# BPU_display-v1d-28inch.net
KiCad netlist of a schematic drawn in EAGLE
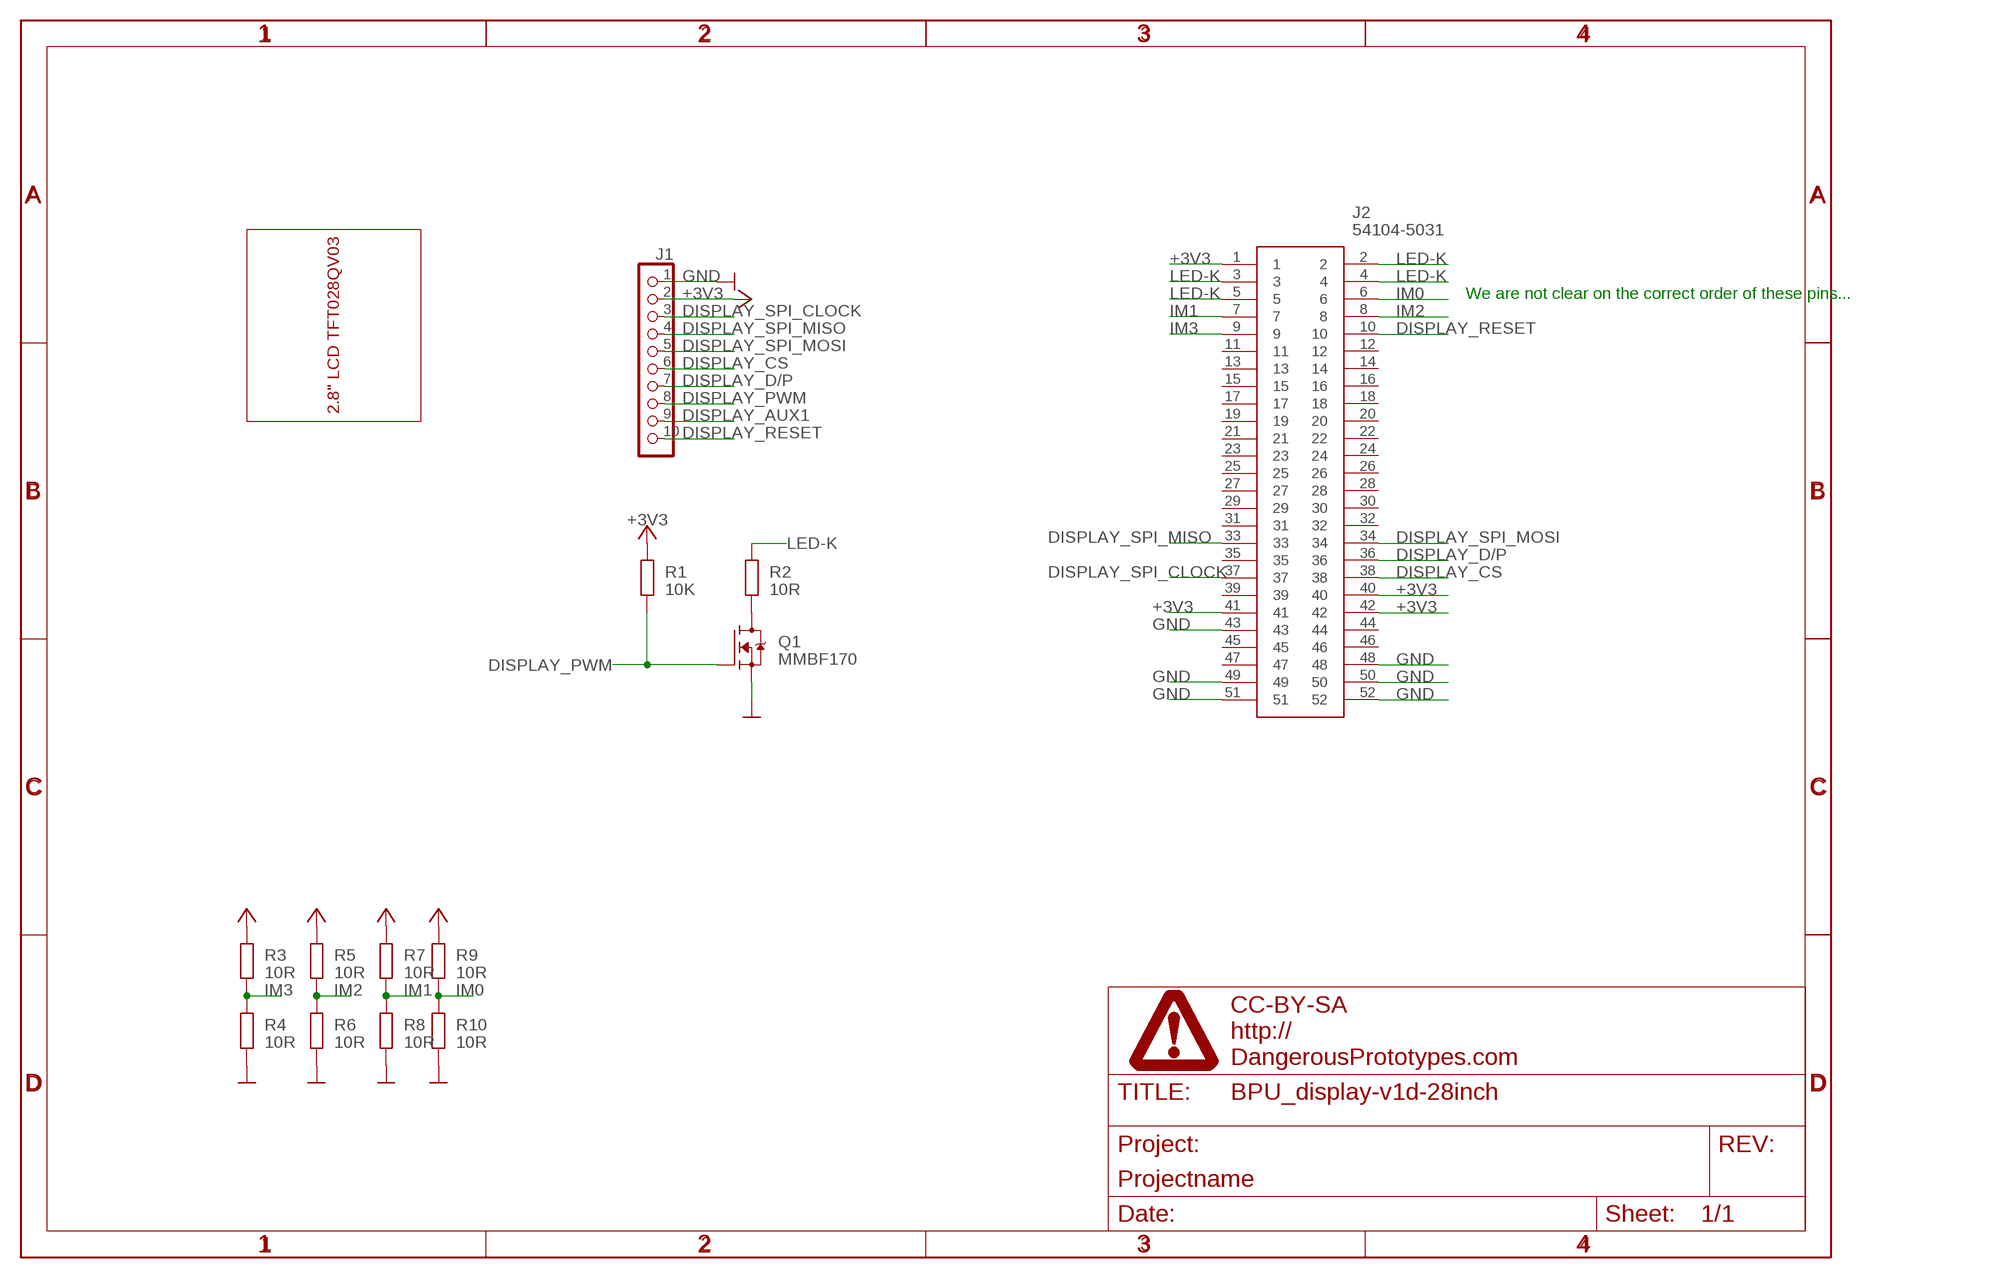
[diagram p0: schematic, sheet 1]

(export (version "E")
  (design (tool "Eeschema 10.0.6"))
  (components
    (comp (ref "J1")
      (value "CON-FPC_X05B20L10T")
      (footprint "eagle-import:X05B20L10T")
      (libsource (lib "eagle-import") (part "CON-FPC_X05B20L10T"))
    )
    (comp (ref "J2")
      (value "54104-5031")
      (footprint "eagle-import:541045031")
      (fields (field (name "MOUSER_PART_NUMBER") "538-54104-5031"))
      (libsource (lib "eagle-import") (part "54104-5031"))
    )
    (comp (ref "PAGE1")
      (value "FRAME_DINA4_L")
      (footprint "eagle-import:DP_LOGO")
      (fields
        (field (name "LICENSE") "CC-BY-SA")
        (field (name "URL1") "http://")
        (field (name "URL2") "DangerousPrototypes.com")
        (field (name "PROJECT") "Projectname")
      )
      (libsource (lib "eagle-import") (part "FRAME_DINA4_L"))
    )
    (comp (ref "Q1")
      (value "MMBF170")
      (footprint "eagle-import:SOT-23")
      (libsource (lib "eagle-import") (part "TRANSISTOR_FET_BS170-SOT-23"))
    )
    (comp (ref "R1")
      (value "10K")
      (footprint "eagle-import:R0603")
      (libsource (lib "eagle-import") (part "R-EU_R0603"))
    )
    (comp (ref "R2")
      (value "10R")
      (footprint "eagle-import:R0603")
      (libsource (lib "eagle-import") (part "R-EU_R0603"))
    )
    (comp (ref "R3")
      (value "10R")
      (footprint "eagle-import:R0603")
      (libsource (lib "eagle-import") (part "R-EU_R0603"))
    )
    (comp (ref "R4")
      (value "10R")
      (footprint "eagle-import:R0603")
      (libsource (lib "eagle-import") (part "R-EU_R0603"))
    )
    (comp (ref "R5")
      (value "10R")
      (footprint "eagle-import:R0603")
      (libsource (lib "eagle-import") (part "R-EU_R0603"))
    )
    (comp (ref "R6")
      (value "10R")
      (footprint "eagle-import:R0603")
      (libsource (lib "eagle-import") (part "R-EU_R0603"))
    )
    (comp (ref "R7")
      (value "10R")
      (footprint "eagle-import:R0603")
      (libsource (lib "eagle-import") (part "R-EU_R0603"))
    )
    (comp (ref "R8")
      (value "10R")
      (footprint "eagle-import:R0603")
      (libsource (lib "eagle-import") (part "R-EU_R0603"))
    )
    (comp (ref "R9")
      (value "10R")
      (footprint "eagle-import:R0603")
      (libsource (lib "eagle-import") (part "R-EU_R0603"))
    )
    (comp (ref "R10")
      (value "10R")
      (footprint "eagle-import:R0603")
      (libsource (lib "eagle-import") (part "R-EU_R0603"))
    )
    (comp (ref "U$1")
      (value "LCDS")
      (footprint "eagle-import:2.8INCHLCD")
      (libsource (lib "eagle-import") (part "LCDS"))
    )
  )
  (nets
    (net (code "1") (name "/DISPLAY_AUX1") (class "Default")
      (node (ref "J1") (pin "9") (pinfunction "9_9") (pintype "passive"))
    )
    (net (code "2") (name "/DISPLAY_CS") (class "Default")
      (node (ref "J1") (pin "6") (pinfunction "6_6") (pintype "passive"))
      (node (ref "J2") (pin "38") (pinfunction "38_38") (pintype "bidirectional"))
    )
    (net (code "3") (name "/DISPLAY_D{slash}P") (class "Default")
      (node (ref "J1") (pin "7") (pinfunction "7_7") (pintype "passive"))
      (node (ref "J2") (pin "36") (pinfunction "36_36") (pintype "bidirectional"))
    )
    (net (code "4") (name "/DISPLAY_PWM") (class "Default")
      (node (ref "J1") (pin "8") (pinfunction "8_8") (pintype "passive"))
      (node (ref "Q1") (pin "1") (pinfunction "G_1") (pintype "passive"))
      (node (ref "R1") (pin "1") (pinfunction "1_1") (pintype "passive"))
    )
    (net (code "5") (name "/DISPLAY_RESET") (class "Default")
      (node (ref "J1") (pin "10") (pinfunction "10_10") (pintype "passive"))
      (node (ref "J2") (pin "10") (pinfunction "10_10") (pintype "bidirectional"))
    )
    (net (code "6") (name "/DISPLAY_SPI_CLOCK") (class "Default")
      (node (ref "J1") (pin "3") (pinfunction "3_3") (pintype "passive"))
      (node (ref "J2") (pin "37") (pinfunction "37_37") (pintype "bidirectional"))
    )
    (net (code "7") (name "/DISPLAY_SPI_MISO") (class "Default")
      (node (ref "J1") (pin "4") (pinfunction "4_4") (pintype "passive"))
      (node (ref "J2") (pin "33") (pinfunction "33_33") (pintype "bidirectional"))
    )
    (net (code "8") (name "/DISPLAY_SPI_MOSI") (class "Default")
      (node (ref "J1") (pin "5") (pinfunction "5_5") (pintype "passive"))
      (node (ref "J2") (pin "34") (pinfunction "34_34") (pintype "bidirectional"))
    )
    (net (code "9") (name "/IM0") (class "Default")
      (node (ref "J2") (pin "6") (pinfunction "6_6") (pintype "bidirectional"))
      (node (ref "R10") (pin "2") (pinfunction "2_2") (pintype "passive"))
      (node (ref "R9") (pin "1") (pinfunction "1_1") (pintype "passive"))
    )
    (net (code "10") (name "/IM1") (class "Default")
      (node (ref "J2") (pin "7") (pinfunction "7_7") (pintype "bidirectional"))
      (node (ref "R7") (pin "1") (pinfunction "1_1") (pintype "passive"))
      (node (ref "R8") (pin "2") (pinfunction "2_2") (pintype "passive"))
    )
    (net (code "11") (name "/IM2") (class "Default")
      (node (ref "J2") (pin "8") (pinfunction "8_8") (pintype "bidirectional"))
      (node (ref "R5") (pin "1") (pinfunction "1_1") (pintype "passive"))
      (node (ref "R6") (pin "2") (pinfunction "2_2") (pintype "passive"))
    )
    (net (code "12") (name "/IM3") (class "Default")
      (node (ref "J2") (pin "9") (pinfunction "9_9") (pintype "bidirectional"))
      (node (ref "R3") (pin "1") (pinfunction "1_1") (pintype "passive"))
      (node (ref "R4") (pin "2") (pinfunction "2_2") (pintype "passive"))
    )
    (net (code "13") (name "/LED-K") (class "Default")
      (node (ref "J2") (pin "2") (pinfunction "2_2") (pintype "bidirectional"))
      (node (ref "J2") (pin "3") (pinfunction "3_3") (pintype "bidirectional"))
      (node (ref "J2") (pin "4") (pinfunction "4_4") (pintype "bidirectional"))
      (node (ref "J2") (pin "5") (pinfunction "5_5") (pintype "bidirectional"))
      (node (ref "R2") (pin "2") (pinfunction "2_2") (pintype "passive"))
    )
    (net (code "14") (name "Net-(Q1-D)") (class "Default")
      (node (ref "Q1") (pin "3") (pinfunction "D_3") (pintype "passive"))
      (node (ref "R2") (pin "1") (pinfunction "1_1") (pintype "passive"))
    )
    (net (code "15") (name "SUPPLY_+3V3") (class "Default")
      (node (ref "J1") (pin "2") (pinfunction "2_2") (pintype "passive"))
      (node (ref "J2") (pin "1") (pinfunction "1_1") (pintype "bidirectional"))
      (node (ref "J2") (pin "40") (pinfunction "40_40") (pintype "bidirectional"))
      (node (ref "J2") (pin "41") (pinfunction "41_41") (pintype "bidirectional"))
      (node (ref "J2") (pin "42") (pinfunction "42_42") (pintype "bidirectional"))
      (node (ref "R1") (pin "2") (pinfunction "2_2") (pintype "passive"))
      (node (ref "R3") (pin "2") (pinfunction "2_2") (pintype "passive"))
      (node (ref "R5") (pin "2") (pinfunction "2_2") (pintype "passive"))
      (node (ref "R7") (pin "2") (pinfunction "2_2") (pintype "passive"))
      (node (ref "R9") (pin "2") (pinfunction "2_2") (pintype "passive"))
    )
    (net (code "16") (name "SUPPLY_GND") (class "Default")
      (node (ref "J1") (pin "1") (pinfunction "1_1") (pintype "passive"))
      (node (ref "J2") (pin "43") (pinfunction "43_43") (pintype "bidirectional"))
      (node (ref "J2") (pin "48") (pinfunction "48_48") (pintype "bidirectional"))
      (node (ref "J2") (pin "49") (pinfunction "49_49") (pintype "bidirectional"))
      (node (ref "J2") (pin "50") (pinfunction "50_50") (pintype "bidirectional"))
      (node (ref "J2") (pin "51") (pinfunction "51_51") (pintype "bidirectional"))
      (node (ref "J2") (pin "52") (pinfunction "52_52") (pintype "bidirectional"))
      (node (ref "Q1") (pin "2") (pinfunction "S_2") (pintype "passive"))
      (node (ref "R10") (pin "1") (pinfunction "1_1") (pintype "passive"))
      (node (ref "R4") (pin "1") (pinfunction "1_1") (pintype "passive"))
      (node (ref "R6") (pin "1") (pinfunction "1_1") (pintype "passive"))
      (node (ref "R8") (pin "1") (pinfunction "1_1") (pintype "passive"))
    )
    (net (code "17") (name "unconnected-(J2-Pad11)") (class "Default")
      (node (ref "J2") (pin "11") (pinfunction "11_11") (pintype "bidirectional"))
    )
    (net (code "18") (name "unconnected-(J2-Pad12)") (class "Default")
      (node (ref "J2") (pin "12") (pinfunction "12_12") (pintype "bidirectional"))
    )
    (net (code "19") (name "unconnected-(J2-Pad13)") (class "Default")
      (node (ref "J2") (pin "13") (pinfunction "13_13") (pintype "bidirectional"))
    )
    (net (code "20") (name "unconnected-(J2-Pad14)") (class "Default")
      (node (ref "J2") (pin "14") (pinfunction "14_14") (pintype "bidirectional"))
    )
    (net (code "21") (name "unconnected-(J2-Pad15)") (class "Default")
      (node (ref "J2") (pin "15") (pinfunction "15_15") (pintype "bidirectional"))
    )
    (net (code "22") (name "unconnected-(J2-Pad16)") (class "Default")
      (node (ref "J2") (pin "16") (pinfunction "16_16") (pintype "bidirectional"))
    )
    (net (code "23") (name "unconnected-(J2-Pad17)") (class "Default")
      (node (ref "J2") (pin "17") (pinfunction "17_17") (pintype "bidirectional"))
    )
    (net (code "24") (name "unconnected-(J2-Pad18)") (class "Default")
      (node (ref "J2") (pin "18") (pinfunction "18_18") (pintype "bidirectional"))
    )
    (net (code "25") (name "unconnected-(J2-Pad19)") (class "Default")
      (node (ref "J2") (pin "19") (pinfunction "19_19") (pintype "bidirectional"))
    )
    (net (code "26") (name "unconnected-(J2-Pad20)") (class "Default")
      (node (ref "J2") (pin "20") (pinfunction "20_20") (pintype "bidirectional"))
    )
    (net (code "27") (name "unconnected-(J2-Pad21)") (class "Default")
      (node (ref "J2") (pin "21") (pinfunction "21_21") (pintype "bidirectional"))
    )
    (net (code "28") (name "unconnected-(J2-Pad22)") (class "Default")
      (node (ref "J2") (pin "22") (pinfunction "22_22") (pintype "bidirectional"))
    )
    (net (code "29") (name "unconnected-(J2-Pad23)") (class "Default")
      (node (ref "J2") (pin "23") (pinfunction "23_23") (pintype "bidirectional"))
    )
    (net (code "30") (name "unconnected-(J2-Pad24)") (class "Default")
      (node (ref "J2") (pin "24") (pinfunction "24_24") (pintype "bidirectional"))
    )
    (net (code "31") (name "unconnected-(J2-Pad25)") (class "Default")
      (node (ref "J2") (pin "25") (pinfunction "25_25") (pintype "bidirectional"))
    )
    (net (code "32") (name "unconnected-(J2-Pad26)") (class "Default")
      (node (ref "J2") (pin "26") (pinfunction "26_26") (pintype "bidirectional"))
    )
    (net (code "33") (name "unconnected-(J2-Pad27)") (class "Default")
      (node (ref "J2") (pin "27") (pinfunction "27_27") (pintype "bidirectional"))
    )
    (net (code "34") (name "unconnected-(J2-Pad28)") (class "Default")
      (node (ref "J2") (pin "28") (pinfunction "28_28") (pintype "bidirectional"))
    )
    (net (code "35") (name "unconnected-(J2-Pad29)") (class "Default")
      (node (ref "J2") (pin "29") (pinfunction "29_29") (pintype "bidirectional"))
    )
    (net (code "36") (name "unconnected-(J2-Pad30)") (class "Default")
      (node (ref "J2") (pin "30") (pinfunction "30_30") (pintype "bidirectional"))
    )
    (net (code "37") (name "unconnected-(J2-Pad31)") (class "Default")
      (node (ref "J2") (pin "31") (pinfunction "31_31") (pintype "bidirectional"))
    )
    (net (code "38") (name "unconnected-(J2-Pad32)") (class "Default")
      (node (ref "J2") (pin "32") (pinfunction "32_32") (pintype "bidirectional"))
    )
    (net (code "39") (name "unconnected-(J2-Pad35)") (class "Default")
      (node (ref "J2") (pin "35") (pinfunction "35_35") (pintype "bidirectional"))
    )
    (net (code "40") (name "unconnected-(J2-Pad39)") (class "Default")
      (node (ref "J2") (pin "39") (pinfunction "39_39") (pintype "bidirectional"))
    )
    (net (code "41") (name "unconnected-(J2-Pad44)") (class "Default")
      (node (ref "J2") (pin "44") (pinfunction "44_44") (pintype "bidirectional"))
    )
    (net (code "42") (name "unconnected-(J2-Pad45)") (class "Default")
      (node (ref "J2") (pin "45") (pinfunction "45_45") (pintype "bidirectional"))
    )
    (net (code "43") (name "unconnected-(J2-Pad46)") (class "Default")
      (node (ref "J2") (pin "46") (pinfunction "46_46") (pintype "bidirectional"))
    )
    (net (code "44") (name "unconnected-(J2-Pad47)") (class "Default")
      (node (ref "J2") (pin "47") (pinfunction "47_47") (pintype "bidirectional"))
    )
  )
)
